# eloszt.net
KiCad netlist of a schematic drawn in EAGLE
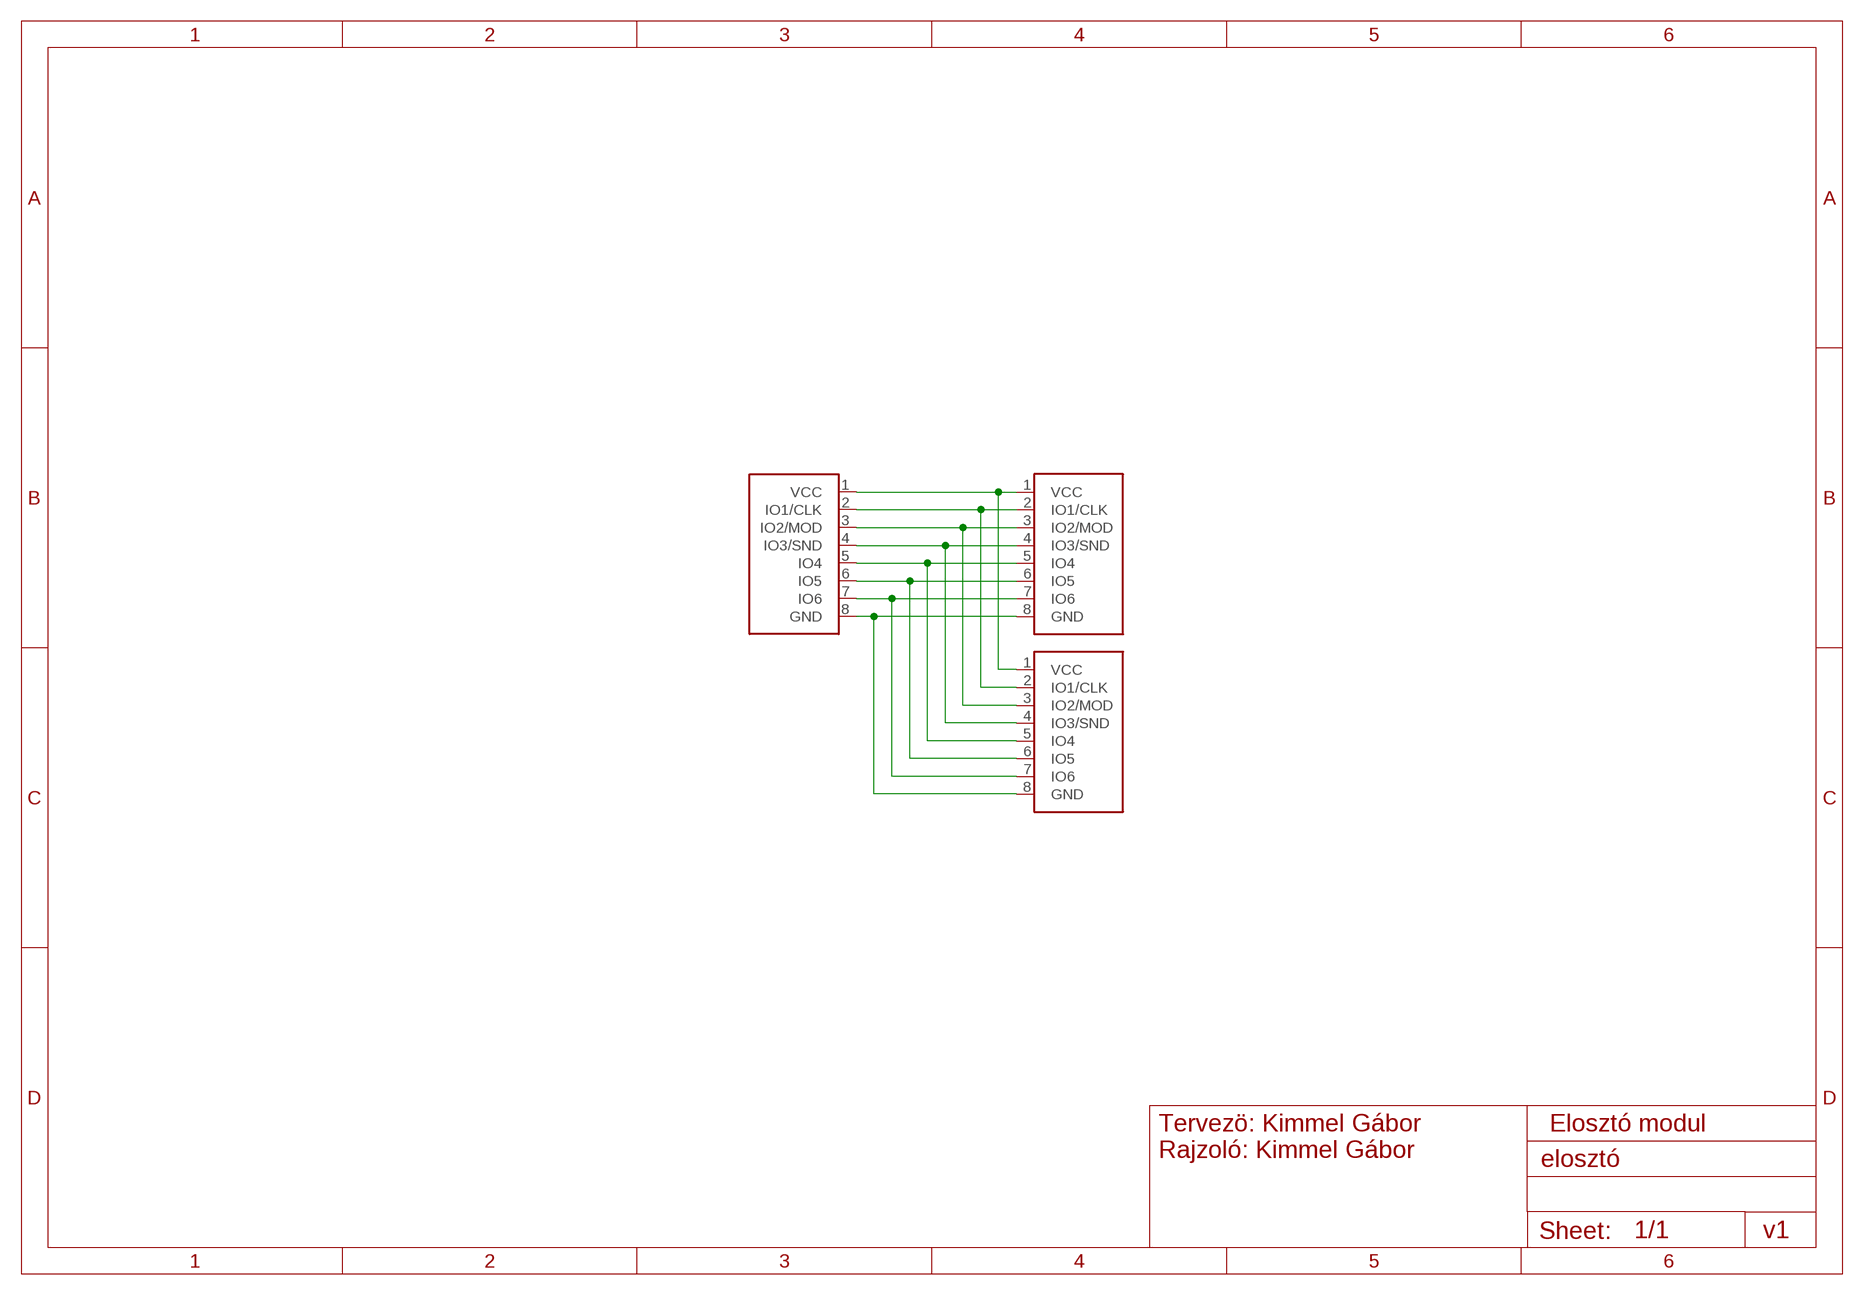
[diagram p0: schematic, sheet 1]

(export (version "E")
  (design (tool "Eeschema 10.0.6"))
  (components
    (comp (ref "U$1")
      (value "GANZ-CONNECTOR")
      (footprint "eagle-import:FE08W")
      (libsource (lib "eagle-import") (part "GANZ-CONNECTOR"))
    )
    (comp (ref "U$2")
      (value "GANZ-CONNECTOR-OUT")
      (footprint "eagle-import:MA08-1W")
      (libsource (lib "eagle-import") (part "GANZ-CONNECTOR-OUT"))
    )
    (comp (ref "U$3")
      (value "GANZ-CONNECTOR-OUT")
      (footprint "eagle-import:MA08-1W")
      (libsource (lib "eagle-import") (part "GANZ-CONNECTOR-OUT"))
    )
  )
  (nets
    (net (code "1") (name "Net-(U$1-GND)") (class "Default")
      (node (ref "U$1") (pin "8") (pinfunction "GND_8") (pintype "bidirectional"))
      (node (ref "U$2") (pin "8") (pinfunction "GND_8") (pintype "bidirectional"))
      (node (ref "U$3") (pin "8") (pinfunction "GND_8") (pintype "bidirectional"))
    )
    (net (code "2") (name "Net-(U$1-IO1{slash}CLK)") (class "Default")
      (node (ref "U$1") (pin "2") (pinfunction "IO1/CLK_2") (pintype "bidirectional"))
      (node (ref "U$2") (pin "2") (pinfunction "IO1/CLK_2") (pintype "bidirectional"))
      (node (ref "U$3") (pin "2") (pinfunction "IO1/CLK_2") (pintype "bidirectional"))
    )
    (net (code "3") (name "Net-(U$1-IO2{slash}MOD)") (class "Default")
      (node (ref "U$1") (pin "3") (pinfunction "IO2/MOD_3") (pintype "bidirectional"))
      (node (ref "U$2") (pin "3") (pinfunction "IO2/MOD_3") (pintype "bidirectional"))
      (node (ref "U$3") (pin "3") (pinfunction "IO2/MOD_3") (pintype "bidirectional"))
    )
    (net (code "4") (name "Net-(U$1-IO3{slash}SND)") (class "Default")
      (node (ref "U$1") (pin "4") (pinfunction "IO3/SND_4") (pintype "bidirectional"))
      (node (ref "U$2") (pin "4") (pinfunction "IO3/SND_4") (pintype "bidirectional"))
      (node (ref "U$3") (pin "4") (pinfunction "IO3/SND_4") (pintype "bidirectional"))
    )
    (net (code "5") (name "Net-(U$1-IO4)") (class "Default")
      (node (ref "U$1") (pin "5") (pinfunction "IO4_5") (pintype "bidirectional"))
      (node (ref "U$2") (pin "5") (pinfunction "IO4_5") (pintype "bidirectional"))
      (node (ref "U$3") (pin "5") (pinfunction "IO4_5") (pintype "bidirectional"))
    )
    (net (code "6") (name "Net-(U$1-IO5)") (class "Default")
      (node (ref "U$1") (pin "6") (pinfunction "IO5_6") (pintype "bidirectional"))
      (node (ref "U$2") (pin "6") (pinfunction "IO5_6") (pintype "bidirectional"))
      (node (ref "U$3") (pin "6") (pinfunction "IO5_6") (pintype "bidirectional"))
    )
    (net (code "7") (name "Net-(U$1-IO6)") (class "Default")
      (node (ref "U$1") (pin "7") (pinfunction "IO6_7") (pintype "bidirectional"))
      (node (ref "U$2") (pin "7") (pinfunction "IO6_7") (pintype "bidirectional"))
      (node (ref "U$3") (pin "7") (pinfunction "IO6_7") (pintype "bidirectional"))
    )
    (net (code "8") (name "Net-(U$1-VCC)") (class "Default")
      (node (ref "U$1") (pin "1") (pinfunction "VCC_1") (pintype "bidirectional"))
      (node (ref "U$2") (pin "1") (pinfunction "VCC_1") (pintype "bidirectional"))
      (node (ref "U$3") (pin "1") (pinfunction "VCC_1") (pintype "bidirectional"))
    )
  )
)
